# 5-Latching_Delay.net
KiCad netlist of a schematic drawn in Altium Designer
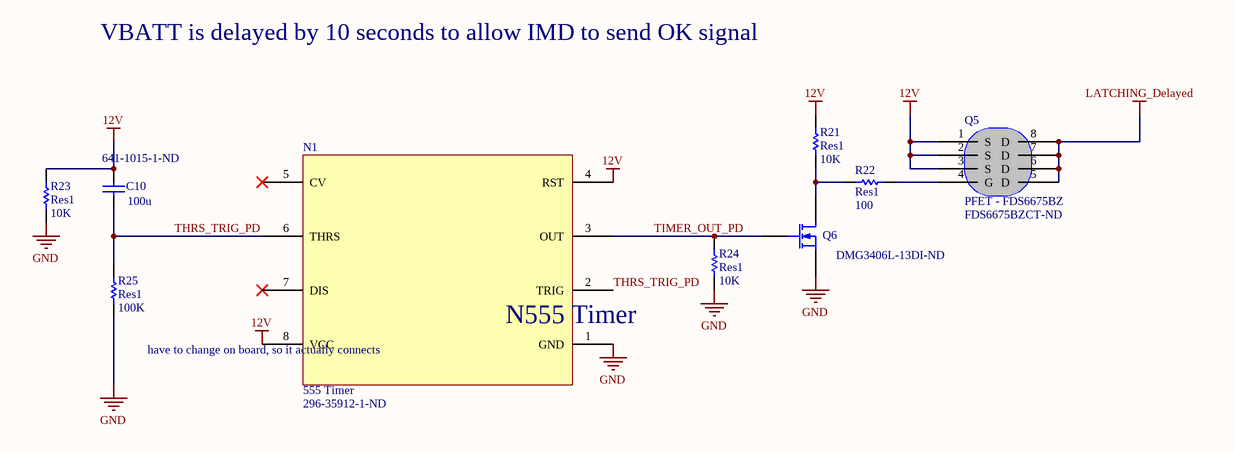
[diagram p0: 5-Latching Delay.SchDoc]

(export (version "E")
  (design (tool "Eeschema 10.0.6"))
  (components
    (comp (ref "C10")
      (value "100u")
      (footprint "C1210")
      (description "CAP CER 100UF 6.3V X5R 1206")
      (fields
        (field (name "MANUFACTURER") "Murata Electronics North America")
        (field (name "MANUFACTURER PART NUMBER") "GRM31CR60J107ME39K")
        (field (name "SUPPLIER PART NUMBER 1") "641-1015-1-ND")
      )
      (libsource (lib "Miscellaneous Devices") (part "Cap"))
    )
    (comp (ref "N1")
      (value "555 Timer")
      (footprint "SO8_M")
      (description "IC OSC SGL TIMER 100KHZ 8-SOIC")
      (fields
        (field (name "SUPPLIER PART NUMBER 1") "296-35912-1-ND")
        (field (name "MANUFACTURER") "Texas Instruments")
        (field (name "MANUFACTURER PART NUMBER") "NE555DRG4")
      )
      (libsource (lib "Latching  2017 - IMD") (part "555 Timer"))
    )
    (comp (ref "Q5")
      (value "PFET - FDS6675BZ")
      (footprint "SOIC127P600X175-8N")
      (description "MOSFET P-CH 8-SOIC")
      (fields
        (field (name "SUPPLIER PART NUMBER 1") "FDS6675BZCT-ND")
        (field (name "MANUFACTURER") "Fairchild/ON Semiconductor")
        (field (name "MANUFACTURER PART NUMBER") "FDS6675BZ")
      )
      (libsource (lib "Latching_Reset_Library") (part "MOSFET"))
    )
    (comp (ref "Q6")
      (value "~")
      (footprint "SOT-23_N")
      (description "N-Channel MOSFET")
      (fields
        (field (name "MANUFACTURER") "Infineon Technologies")
        (field (name "MANUFACTURER PART NUMBER") "IPD075N03L G")
        (field (name "SUPPLIER PART NUMBER 1") "DMG3406L-13DI-ND")
        (field (name "PUBLISHER") "Altium Limited")
      )
      (libsource (lib "Miscellaneous Devices") (part "MOSFET-N"))
    )
    (comp (ref "R21")
      (value "Res1")
      (footprint "1608[0603]")
      (description "RES SMD 10K OHM 5% 1/4W 0603")
      (fields
        (field (name "ALTIUM_VALUE") "10K")
        (field (name "MANUFACTURER") "Rohm Semiconductor")
        (field (name "MANUFACTURER PART NUMBER") "ESR03EZPJ103")
        (field (name "PUBLISHER") "Altium Limited")
      )
      (libsource (lib "Miscellaneous Devices") (part "Res1"))
    )
    (comp (ref "R22")
      (value "Res1")
      (footprint "1608[0603]")
      (description "RES SMD 100 OHM 5% 1/4W 0603")
      (fields
        (field (name "ALTIUM_VALUE") "100")
        (field (name "MANUFACTURER") "Rohm Semiconductor")
        (field (name "MANUFACTURER PART NUMBER") "ESR03EZPJ101")
        (field (name "PUBLISHER") "Altium Limited")
      )
      (libsource (lib "Miscellaneous Devices") (part "Res1"))
    )
    (comp (ref "R23")
      (value "Res1")
      (footprint "1608[0603]")
      (description "RES SMD 10K OHM 5% 1/4W 0603")
      (fields
        (field (name "ALTIUM_VALUE") "10K")
        (field (name "MANUFACTURER") "Rohm Semiconductor")
        (field (name "MANUFACTURER PART NUMBER") "ESR03EZPJ103")
        (field (name "PUBLISHER") "Altium Limited")
      )
      (libsource (lib "Miscellaneous Devices") (part "Res1"))
    )
    (comp (ref "R24")
      (value "Res1")
      (footprint "1608[0603]")
      (description "RES SMD 10K OHM 5% 1/4W 0603")
      (fields
        (field (name "ALTIUM_VALUE") "10K")
        (field (name "MANUFACTURER") "Rohm Semiconductor")
        (field (name "MANUFACTURER PART NUMBER") "ESR03EZPJ103")
        (field (name "PUBLISHER") "Altium Limited")
      )
      (libsource (lib "Miscellaneous Devices") (part "Res1"))
    )
    (comp (ref "R25")
      (value "Res1")
      (footprint "1608[0603]")
      (description "RES SMD 33K OHM 5% 1/4W 0603")
      (fields
        (field (name "ALTIUM_VALUE") "100K")
        (field (name "MANUFACTURER") "Rohm Semiconductor")
        (field (name "MANUFACTURER PART NUMBER") "ESR03EZPJ333")
        (field (name "PUBLISHER") "Altium Limited")
      )
      (libsource (lib "Miscellaneous Devices") (part "Res1"))
    )
  )
  (nets
    (net (code "1") (name "/THRS_TRIG_PD") (class "Default")
      (node (ref "C10") (pin "2") (pinfunction "2_2") (pintype "passive"))
      (node (ref "N1") (pin "2") (pinfunction "TRIG_2") (pintype "passive"))
      (node (ref "N1") (pin "6") (pinfunction "THRS_6") (pintype "passive"))
      (node (ref "R25") (pin "2") (pinfunction "2_2") (pintype "passive"))
    )
    (net (code "2") (name "/TIMER_OUT_PD") (class "Default")
      (node (ref "N1") (pin "3") (pinfunction "OUT_3") (pintype "passive"))
      (node (ref "Q6") (pin "1") (pinfunction "G_1") (pintype "passive"))
      (node (ref "R24") (pin "2") (pinfunction "2_2") (pintype "passive"))
    )
    (net (code "3") (name "12V") (class "Default")
      (node (ref "C10") (pin "1") (pinfunction "1_1") (pintype "passive"))
      (node (ref "N1") (pin "4") (pinfunction "RST_4") (pintype "passive"))
      (node (ref "N1") (pin "8") (pinfunction "VCC_8") (pintype "passive"))
      (node (ref "Q5") (pin "1") (pinfunction "S_1") (pintype "passive"))
      (node (ref "Q5") (pin "2") (pinfunction "S_2") (pintype "passive"))
      (node (ref "Q5") (pin "3") (pinfunction "S_3") (pintype "passive"))
      (node (ref "R21") (pin "2") (pinfunction "2_2") (pintype "passive"))
      (node (ref "R23") (pin "2") (pinfunction "2_2") (pintype "passive"))
    )
    (net (code "4") (name "GND") (class "Default")
      (node (ref "N1") (pin "1") (pinfunction "GND_1") (pintype "passive"))
      (node (ref "Q6") (pin "2") (pinfunction "S_2") (pintype "passive"))
      (node (ref "R23") (pin "1") (pinfunction "1_1") (pintype "passive"))
      (node (ref "R24") (pin "1") (pinfunction "1_1") (pintype "passive"))
      (node (ref "R25") (pin "1") (pinfunction "1_1") (pintype "passive"))
    )
    (net (code "5") (name "LATCHING_Delayed") (class "Default")
      (node (ref "Q5") (pin "5") (pinfunction "D_5") (pintype "passive"))
      (node (ref "Q5") (pin "6") (pinfunction "D_6") (pintype "passive"))
      (node (ref "Q5") (pin "7") (pinfunction "D_7") (pintype "passive"))
      (node (ref "Q5") (pin "8") (pinfunction "D_8") (pintype "passive"))
    )
    (net (code "6") (name "Net-(Q5-G)") (class "Default")
      (node (ref "Q5") (pin "4") (pinfunction "G_4") (pintype "passive"))
      (node (ref "R22") (pin "2") (pinfunction "2_2") (pintype "passive"))
    )
    (net (code "7") (name "Net-(Q6-D)") (class "Default")
      (node (ref "Q6") (pin "3") (pinfunction "D_3") (pintype "passive"))
      (node (ref "R21") (pin "1") (pinfunction "1_1") (pintype "passive"))
      (node (ref "R22") (pin "1") (pinfunction "1_1") (pintype "passive"))
    )
    (net (code "8") (name "unconnected-(N1-CV-Pad5)") (class "Default")
      (node (ref "N1") (pin "5") (pinfunction "CV_5") (pintype "passive+no_connect"))
    )
    (net (code "9") (name "unconnected-(N1-DIS-Pad7)") (class "Default")
      (node (ref "N1") (pin "7") (pinfunction "DIS_7") (pintype "passive+no_connect"))
    )
  )
)
